# Schematic.net
KiCad netlist of a schematic drawn in Altium Designer
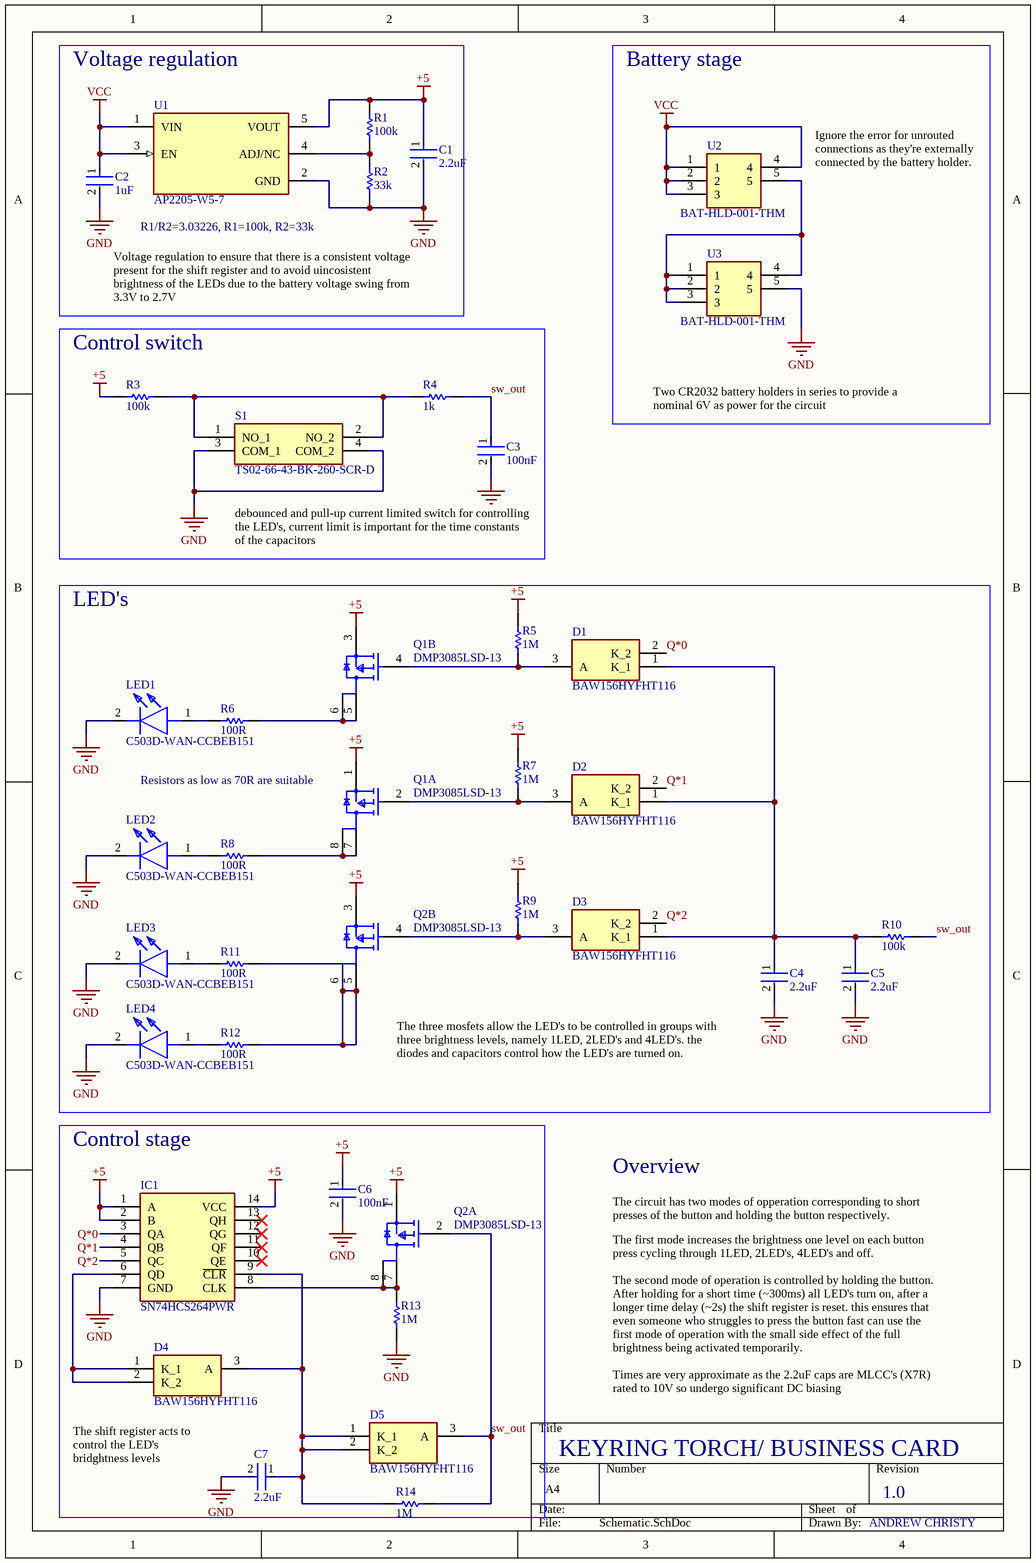
[diagram p0: Schematic.SchDoc]

(export (version "E")
  (design (tool "Eeschema 10.0.6"))
  (components
    (comp (ref "C1")
      (value "2.2uF")
      (footprint "FP-GRM188-0_1-e0_2_0_55-IPC_A")
      (description "Chip Multilayer Ceramic Capacitors for General Purpose, 0603, 10uF, X5R, 15%, 20%, 6.3V")
      (fields (field (name "VOLTAGE") "6.3V") (field (name "TOLERANCE") "20%"))
      (libsource (lib "Altium Content Vault") (part "02cd4be3c70576c341d710602a673aa"))
    )
    (comp (ref "C2")
      (value "1uF")
      (footprint "FP-GRM188-0_1-e0_2_0_55-IPC_A")
      (description "Chip Multilayer Ceramic Capacitors for General Purpose, 0603, 10uF, X5R, 15%, 20%, 6.3V")
      (fields (field (name "VOLTAGE") "6.3V") (field (name "TOLERANCE") "20%"))
      (libsource (lib "Altium Content Vault") (part "02cd4be3c70576c341d710602a673aa"))
    )
    (comp (ref "C3")
      (value "100nF")
      (footprint "FP-GRM188-0_1-e0_2_0_55-IPC_A")
      (description "Chip Multilayer Ceramic Capacitors for General Purpose, 0603, 10uF, X5R, 15%, 20%, 6.3V")
      (fields (field (name "VOLTAGE") "6.3V") (field (name "TOLERANCE") "20%"))
      (libsource (lib "Altium Content Vault") (part "02cd4be3c70576c341d710602a673aa"))
    )
    (comp (ref "C4")
      (value "2.2uF")
      (footprint "FP-GRM188-0_1-e0_2_0_55-IPC_A")
      (description "Chip Multilayer Ceramic Capacitors for General Purpose, 0603, 10uF, X5R, 15%, 20%, 6.3V")
      (fields (field (name "VOLTAGE") "6.3V") (field (name "TOLERANCE") "20%"))
      (libsource (lib "Altium Content Vault") (part "02cd4be3c70576c341d710602a673aa"))
    )
    (comp (ref "C5")
      (value "2.2uF")
      (footprint "FP-GRM188-0_1-e0_2_0_55-IPC_A")
      (description "Chip Multilayer Ceramic Capacitors for General Purpose, 0603, 10uF, X5R, 15%, 20%, 6.3V")
      (fields (field (name "VOLTAGE") "6.3V") (field (name "TOLERANCE") "20%"))
      (libsource (lib "Altium Content Vault") (part "02cd4be3c70576c341d710602a673aa"))
    )
    (comp (ref "C6")
      (value "100nF")
      (footprint "FP-GRM188-0_1-e0_2_0_55-IPC_A")
      (description "Chip Multilayer Ceramic Capacitors for General Purpose, 0603, 10uF, X5R, 15%, 20%, 6.3V")
      (fields (field (name "VOLTAGE") "6.3V") (field (name "TOLERANCE") "20%"))
      (libsource (lib "Altium Content Vault") (part "02cd4be3c70576c341d710602a673aa"))
    )
    (comp (ref "C7")
      (value "2.2uF")
      (footprint "FP-GRM188-0_1-e0_2_0_55-IPC_A")
      (description "Chip Multilayer Ceramic Capacitors for General Purpose, 0603, 10uF, X5R, 15%, 20%, 6.3V")
      (fields (field (name "VOLTAGE") "6.3V") (field (name "TOLERANCE") "20%"))
      (libsource (lib "Altium Content Vault") (part "02cd4be3c70576c341d710602a673aa"))
    )
    (comp (ref "D1")
      (value "BAW156HYFHT116")
      (footprint "SamacSys:SOT95P240X115-3N")
      (description "Diode")
      (libsource (lib "SamacSys") (part "BAW156HYFHT116"))
    )
    (comp (ref "D2")
      (value "BAW156HYFHT116")
      (footprint "SamacSys:SOT95P240X115-3N")
      (description "Diode")
      (libsource (lib "SamacSys") (part "BAW156HYFHT116"))
    )
    (comp (ref "D3")
      (value "BAW156HYFHT116")
      (footprint "SamacSys:SOT95P240X115-3N")
      (description "Diode")
      (libsource (lib "SamacSys") (part "BAW156HYFHT116"))
    )
    (comp (ref "D4")
      (value "BAW156HYFHT116")
      (footprint "SamacSys:SOT95P240X115-3N")
      (description "Diode")
      (libsource (lib "") (part "BAW156HYFHT116_1"))
    )
    (comp (ref "D5")
      (value "BAW156HYFHT116")
      (footprint "SamacSys:SOT95P240X115-3N")
      (description "Diode")
      (libsource (lib "") (part "BAW156HYFHT116_1"))
    )
    (comp (ref "IC1")
      (value "SN74HCS264PWR")
      (footprint "SamacSys:SOP65P640X120-14N")
      (description "Integrated Circuit")
      (fields (field (name "MOUSER PART NUMBER") "595-SN74HCS264PWR"))
      (libsource (lib "SamacSys") (part "SN74HCS264PWR"))
    )
    (comp (ref "LED1")
      (value "C503D-WAN-CCBEB151")
      (footprint "SamacSys:C503DWANCCBEB151")
      (description "LED")
      (fields (field (name "MOUSER PART NUMBER") "941-C503DWANCCBEB151"))
      (libsource (lib "SamacSys") (part "C503D-WAN-CCBEB151"))
    )
    (comp (ref "LED2")
      (value "C503D-WAN-CCBEB151")
      (footprint "SamacSys:C503DWANCCBEB151")
      (description "LED")
      (fields (field (name "MOUSER PART NUMBER") "941-C503DWANCCBEB151"))
      (libsource (lib "SamacSys") (part "C503D-WAN-CCBEB151"))
    )
    (comp (ref "LED3")
      (value "C503D-WAN-CCBEB151")
      (footprint "SamacSys:C503DWANCCBEB151")
      (description "LED")
      (fields (field (name "MOUSER PART NUMBER") "941-C503DWANCCBEB151"))
      (libsource (lib "SamacSys") (part "C503D-WAN-CCBEB151"))
    )
    (comp (ref "LED4")
      (value "C503D-WAN-CCBEB151")
      (footprint "SamacSys:C503DWANCCBEB151")
      (description "LED")
      (fields (field (name "MOUSER PART NUMBER") "941-C503DWANCCBEB151"))
      (libsource (lib "SamacSys") (part "C503D-WAN-CCBEB151"))
    )
    (comp (ref "Q1")
      (value "DMP3085LSD-13")
      (footprint "FP-SO-8-MFG")
      (description "MOSFET 2P-CH 30V 3.9A 8SO")
      (fields
        (field (name "OCTOPART") "https://octopart.com/dmp3085lsd-13-diodes+inc.-29925597")
        (field (name "MANUFACTURER") "Diodes Inc.")
      )
      (libsource (lib "Altium Content Vault") (part "942955f0223a51ca7db3cf2ab639610"))
    )
    (comp (ref "Q2")
      (value "DMP3085LSD-13")
      (footprint "FP-SO-8-MFG")
      (description "MOSFET 2P-CH 30V 3.9A 8SO")
      (fields
        (field (name "OCTOPART") "https://octopart.com/dmp3085lsd-13-diodes+inc.-29925597")
        (field (name "MANUFACTURER") "Diodes Inc.")
      )
      (libsource (lib "Altium Content Vault") (part "942955f0223a51ca7db3cf2ab639610"))
    )
    (comp (ref "R1")
      (value "100k")
      (footprint "RESC1609X50X30NL8T20")
      (description "Chip Resistor, 0 Ohm, Jumper, 100 mW, -55 to 155 degC, 0603 (1608 Metric), RoHS, Tape and Reel")
      (fields (field (name "MANUFACTURER") "Vishay Semiconductor"))
      (libsource (lib "Altium Content Vault") (part "RES-2"))
    )
    (comp (ref "R2")
      (value "33k")
      (footprint "RESC1609X50X30NL8T20")
      (description "Chip Resistor, 0 Ohm, Jumper, 100 mW, -55 to 155 degC, 0603 (1608 Metric), RoHS, Tape and Reel")
      (fields (field (name "MANUFACTURER") "Vishay Semiconductor"))
      (libsource (lib "Altium Content Vault") (part "RES-2"))
    )
    (comp (ref "R3")
      (value "100k")
      (footprint "RESC1609X50X30NL8T20")
      (description "Chip Resistor, 0 Ohm, Jumper, 100 mW, -55 to 155 degC, 0603 (1608 Metric), RoHS, Tape and Reel")
      (fields (field (name "MANUFACTURER") "Vishay Semiconductor"))
      (libsource (lib "Altium Content Vault") (part "RES-2"))
    )
    (comp (ref "R4")
      (value "1k")
      (footprint "RESC1609X50X30NL8T20")
      (description "Chip Resistor, 0 Ohm, Jumper, 100 mW, -55 to 155 degC, 0603 (1608 Metric), RoHS, Tape and Reel")
      (fields (field (name "MANUFACTURER") "Vishay Semiconductor"))
      (libsource (lib "Altium Content Vault") (part "RES-2"))
    )
    (comp (ref "R5")
      (value "1M")
      (footprint "RESC1609X50X30NL8T20")
      (description "Chip Resistor, 0 Ohm, Jumper, 100 mW, -55 to 155 degC, 0603 (1608 Metric), RoHS, Tape and Reel")
      (fields (field (name "MANUFACTURER") "Vishay Semiconductor"))
      (libsource (lib "Altium Content Vault") (part "RES-2"))
    )
    (comp (ref "R6")
      (value "100R")
      (footprint "RESC1609X50X30NL8T20")
      (description "Chip Resistor, 0 Ohm, Jumper, 100 mW, -55 to 155 degC, 0603 (1608 Metric), RoHS, Tape and Reel")
      (fields (field (name "MANUFACTURER") "Vishay Semiconductor"))
      (libsource (lib "Altium Content Vault") (part "RES-2"))
    )
    (comp (ref "R7")
      (value "1M")
      (footprint "RESC1609X50X30NL8T20")
      (description "Chip Resistor, 0 Ohm, Jumper, 100 mW, -55 to 155 degC, 0603 (1608 Metric), RoHS, Tape and Reel")
      (fields (field (name "MANUFACTURER") "Vishay Semiconductor"))
      (libsource (lib "Altium Content Vault") (part "RES-2"))
    )
    (comp (ref "R8")
      (value "100R")
      (footprint "RESC1609X50X30NL8T20")
      (description "Chip Resistor, 0 Ohm, Jumper, 100 mW, -55 to 155 degC, 0603 (1608 Metric), RoHS, Tape and Reel")
      (fields (field (name "MANUFACTURER") "Vishay Semiconductor"))
      (libsource (lib "Altium Content Vault") (part "RES-2"))
    )
    (comp (ref "R9")
      (value "1M")
      (footprint "RESC1609X50X30NL8T20")
      (description "Chip Resistor, 0 Ohm, Jumper, 100 mW, -55 to 155 degC, 0603 (1608 Metric), RoHS, Tape and Reel")
      (fields (field (name "MANUFACTURER") "Vishay Semiconductor"))
      (libsource (lib "Altium Content Vault") (part "RES-2"))
    )
    (comp (ref "R10")
      (value "100k")
      (footprint "RESC1609X50X30NL8T20")
      (description "Chip Resistor, 0 Ohm, Jumper, 100 mW, -55 to 155 degC, 0603 (1608 Metric), RoHS, Tape and Reel")
      (fields (field (name "MANUFACTURER") "Vishay Semiconductor"))
      (libsource (lib "Altium Content Vault") (part "RES-2"))
    )
    (comp (ref "R11")
      (value "100R")
      (footprint "RESC1609X50X30NL8T20")
      (description "Chip Resistor, 0 Ohm, Jumper, 100 mW, -55 to 155 degC, 0603 (1608 Metric), RoHS, Tape and Reel")
      (fields (field (name "MANUFACTURER") "Vishay Semiconductor"))
      (libsource (lib "Altium Content Vault") (part "RES-2"))
    )
    (comp (ref "R12")
      (value "100R")
      (footprint "RESC1609X50X30NL8T20")
      (description "Chip Resistor, 0 Ohm, Jumper, 100 mW, -55 to 155 degC, 0603 (1608 Metric), RoHS, Tape and Reel")
      (fields (field (name "MANUFACTURER") "Vishay Semiconductor"))
      (libsource (lib "Altium Content Vault") (part "RES-2"))
    )
    (comp (ref "R13")
      (value "1M")
      (footprint "RESC1609X50X30NL8T20")
      (description "Chip Resistor, 0 Ohm, Jumper, 100 mW, -55 to 155 degC, 0603 (1608 Metric), RoHS, Tape and Reel")
      (fields (field (name "MANUFACTURER") "Vishay Semiconductor"))
      (libsource (lib "Altium Content Vault") (part "RES-2"))
    )
    (comp (ref "R14")
      (value "1M")
      (footprint "RESC1609X50X30NL8T20")
      (description "Chip Resistor, 0 Ohm, Jumper, 100 mW, -55 to 155 degC, 0603 (1608 Metric), RoHS, Tape and Reel")
      (fields (field (name "MANUFACTURER") "Vishay Semiconductor"))
      (libsource (lib "Altium Content Vault") (part "RES-2"))
    )
    (comp (ref "S1")
      (value "TS02-66-43-BK-260-SCR-D")
      (footprint "SamacSys:TS026643BK260SCRD")
      (description "Switch")
      (fields (field (name "MOUSER PART NUMBER") "179-TS026643BK260SCR"))
      (libsource (lib "*") (part "TS02-66-43-BK-260-SCR-D"))
    )
    (comp (ref "U1")
      (value "AP2205-W5-7")
      (footprint "FP-SOT25-MFG")
      (description "IC REG LIN POS ADJ 250MA SOT25")
      (libsource (lib "Altium Content Vault") (part "9429a982aa183f21bc275fe3b3339f7"))
    )
    (comp (ref "U2")
      (value "BAT-HLD-001-THM")
      (footprint "SamacSys:BATHLD001THM")
      (description "Undefined or Miscellaneous")
      (fields (field (name "MOUSER PART NUMBER") "712-BAT-HLD-001-THM"))
      (libsource (lib "*") (part "BAT-HLD-001-THM"))
    )
    (comp (ref "U3")
      (value "BAT-HLD-001-THM")
      (footprint "SamacSys:BATHLD001THM")
      (description "Undefined or Miscellaneous")
      (fields (field (name "MOUSER PART NUMBER") "712-BAT-HLD-001-THM"))
      (libsource (lib "*") (part "BAT-HLD-001-THM"))
    )
  )
  (nets
    (net (code "1") (name "+5") (class "Default")
      (node (ref "C1") (pin "1") (pinfunction "1_1") (pintype "passive"))
      (node (ref "C6") (pin "1") (pinfunction "1_1") (pintype "passive"))
      (node (ref "IC1") (pin "1") (pinfunction "A_1") (pintype "passive"))
      (node (ref "IC1") (pin "14") (pinfunction "VCC_14") (pintype "passive"))
      (node (ref "IC1") (pin "2") (pinfunction "B_2") (pintype "passive"))
      (node (ref "Q1") (pin "1") (pinfunction "S1_1") (pintype "passive"))
      (node (ref "Q1") (pin "3") (pinfunction "S2_3") (pintype "passive"))
      (node (ref "Q2") (pin "1") (pinfunction "S1_1") (pintype "passive"))
      (node (ref "Q2") (pin "3") (pinfunction "S2_3") (pintype "passive"))
      (node (ref "R1") (pin "2") (pinfunction "2_2") (pintype "passive"))
      (node (ref "R3") (pin "2") (pinfunction "2_2") (pintype "passive"))
      (node (ref "R5") (pin "2") (pinfunction "2_2") (pintype "passive"))
      (node (ref "R7") (pin "2") (pinfunction "2_2") (pintype "passive"))
      (node (ref "R9") (pin "2") (pinfunction "2_2") (pintype "passive"))
      (node (ref "U1") (pin "5") (pinfunction "VOUT_5") (pintype "power_in"))
    )
    (net (code "2") (name "/Q*0") (class "Default")
      (node (ref "D1") (pin "2") (pinfunction "K_2_2") (pintype "passive"))
      (node (ref "IC1") (pin "3") (pinfunction "QA_3") (pintype "passive"))
    )
    (net (code "3") (name "/Q*1") (class "Default")
      (node (ref "D2") (pin "2") (pinfunction "K_2_2") (pintype "passive"))
      (node (ref "IC1") (pin "4") (pinfunction "QB_4") (pintype "passive"))
    )
    (net (code "4") (name "/Q*2") (class "Default")
      (node (ref "D3") (pin "2") (pinfunction "K_2_2") (pintype "passive"))
      (node (ref "IC1") (pin "5") (pinfunction "QC_5") (pintype "passive"))
    )
    (net (code "5") (name "/sw_out") (class "Default")
      (node (ref "C3") (pin "1") (pinfunction "1_1") (pintype "passive"))
      (node (ref "D5") (pin "3") (pinfunction "A_3") (pintype "passive"))
      (node (ref "Q2") (pin "2") (pinfunction "G1_2") (pintype "passive"))
      (node (ref "R10") (pin "1") (pinfunction "1_1") (pintype "passive"))
      (node (ref "R14") (pin "1") (pinfunction "1_1") (pintype "passive"))
      (node (ref "R4") (pin "1") (pinfunction "1_1") (pintype "passive"))
    )
    (net (code "6") (name "GND") (class "Default")
      (node (ref "C1") (pin "2") (pinfunction "2_2") (pintype "passive"))
      (node (ref "C2") (pin "2") (pinfunction "2_2") (pintype "passive"))
      (node (ref "C3") (pin "2") (pinfunction "2_2") (pintype "passive"))
      (node (ref "C4") (pin "2") (pinfunction "2_2") (pintype "passive"))
      (node (ref "C5") (pin "2") (pinfunction "2_2") (pintype "passive"))
      (node (ref "C6") (pin "2") (pinfunction "2_2") (pintype "passive"))
      (node (ref "C7") (pin "2") (pinfunction "2_2") (pintype "passive"))
      (node (ref "IC1") (pin "7") (pinfunction "GND_7") (pintype "passive"))
      (node (ref "LED1") (pin "2") (pinfunction "K_2") (pintype "passive"))
      (node (ref "LED2") (pin "2") (pinfunction "K_2") (pintype "passive"))
      (node (ref "LED3") (pin "2") (pinfunction "K_2") (pintype "passive"))
      (node (ref "LED4") (pin "2") (pinfunction "K_2") (pintype "passive"))
      (node (ref "R13") (pin "1") (pinfunction "1_1") (pintype "passive"))
      (node (ref "R2") (pin "1") (pinfunction "1_1") (pintype "passive"))
      (node (ref "S1") (pin "3") (pinfunction "COM_1_3") (pintype "passive"))
      (node (ref "S1") (pin "4") (pinfunction "COM_2_4") (pintype "passive"))
      (node (ref "U1") (pin "2") (pinfunction "GND_2") (pintype "power_in"))
      (node (ref "U3") (pin "5") (pinfunction "5_5") (pintype "passive"))
    )
    (net (code "7") (name "Net-(D1-A)") (class "Default")
      (node (ref "D1") (pin "3") (pinfunction "A_3") (pintype "passive"))
      (node (ref "Q1") (pin "4") (pinfunction "G2_4") (pintype "passive"))
      (node (ref "R5") (pin "1") (pinfunction "1_1") (pintype "passive"))
    )
    (net (code "8") (name "Net-(D1-K_1)") (class "Default")
      (node (ref "C4") (pin "1") (pinfunction "1_1") (pintype "passive"))
      (node (ref "C5") (pin "1") (pinfunction "1_1") (pintype "passive"))
      (node (ref "D1") (pin "1") (pinfunction "K_1_1") (pintype "passive"))
      (node (ref "D2") (pin "1") (pinfunction "K_1_1") (pintype "passive"))
      (node (ref "D3") (pin "1") (pinfunction "K_1_1") (pintype "passive"))
      (node (ref "R10") (pin "2") (pinfunction "2_2") (pintype "passive"))
    )
    (net (code "9") (name "Net-(D2-A)") (class "Default")
      (node (ref "D2") (pin "3") (pinfunction "A_3") (pintype "passive"))
      (node (ref "Q1") (pin "2") (pinfunction "G1_2") (pintype "passive"))
      (node (ref "R7") (pin "1") (pinfunction "1_1") (pintype "passive"))
    )
    (net (code "10") (name "Net-(D3-A)") (class "Default")
      (node (ref "D3") (pin "3") (pinfunction "A_3") (pintype "passive"))
      (node (ref "Q2") (pin "4") (pinfunction "G2_4") (pintype "passive"))
      (node (ref "R9") (pin "1") (pinfunction "1_1") (pintype "passive"))
    )
    (net (code "11") (name "Net-(D4-A)") (class "Default")
      (node (ref "C7") (pin "1") (pinfunction "1_1") (pintype "passive"))
      (node (ref "D4") (pin "3") (pinfunction "A_3") (pintype "passive"))
      (node (ref "D5") (pin "1") (pinfunction "K_1_1") (pintype "passive"))
      (node (ref "D5") (pin "2") (pinfunction "K_2_2") (pintype "passive"))
      (node (ref "IC1") (pin "9") (pinfunction "~{CLR}_9") (pintype "passive"))
      (node (ref "R14") (pin "2") (pinfunction "2_2") (pintype "passive"))
    )
    (net (code "12") (name "Net-(D4-K_1)") (class "Default")
      (node (ref "D4") (pin "1") (pinfunction "K_1_1") (pintype "passive"))
      (node (ref "D4") (pin "2") (pinfunction "K_2_2") (pintype "passive"))
      (node (ref "IC1") (pin "6") (pinfunction "QD_6") (pintype "passive"))
    )
    (net (code "13") (name "Net-(IC1-CLK)") (class "Default")
      (node (ref "IC1") (pin "8") (pinfunction "CLK_8") (pintype "passive"))
      (node (ref "Q2") (pin "7") (pinfunction "D1_7") (pintype "passive"))
      (node (ref "Q2") (pin "8") (pinfunction "D1_8") (pintype "passive"))
      (node (ref "R13") (pin "2") (pinfunction "2_2") (pintype "passive"))
    )
    (net (code "14") (name "Net-(LED1-A)") (class "Default")
      (node (ref "LED1") (pin "1") (pinfunction "A_1") (pintype "passive"))
      (node (ref "R6") (pin "2") (pinfunction "2_2") (pintype "passive"))
    )
    (net (code "15") (name "Net-(LED2-A)") (class "Default")
      (node (ref "LED2") (pin "1") (pinfunction "A_1") (pintype "passive"))
      (node (ref "R8") (pin "2") (pinfunction "2_2") (pintype "passive"))
    )
    (net (code "16") (name "Net-(LED3-A)") (class "Default")
      (node (ref "LED3") (pin "1") (pinfunction "A_1") (pintype "passive"))
      (node (ref "R11") (pin "2") (pinfunction "2_2") (pintype "passive"))
    )
    (net (code "17") (name "Net-(LED4-A)") (class "Default")
      (node (ref "LED4") (pin "1") (pinfunction "A_1") (pintype "passive"))
      (node (ref "R12") (pin "2") (pinfunction "2_2") (pintype "passive"))
    )
    (net (code "18") (name "Net-(Q1A-D1-Pad7)") (class "Default")
      (node (ref "Q1") (pin "7") (pinfunction "D1_7") (pintype "passive"))
      (node (ref "Q1") (pin "8") (pinfunction "D1_8") (pintype "passive"))
      (node (ref "R8") (pin "1") (pinfunction "1_1") (pintype "passive"))
    )
    (net (code "19") (name "Net-(Q1B-D2-Pad5)") (class "Default")
      (node (ref "Q1") (pin "5") (pinfunction "D2_5") (pintype "passive"))
      (node (ref "Q1") (pin "6") (pinfunction "D2_6") (pintype "passive"))
      (node (ref "R6") (pin "1") (pinfunction "1_1") (pintype "passive"))
    )
    (net (code "20") (name "Net-(Q2B-D2-Pad5)") (class "Default")
      (node (ref "Q2") (pin "5") (pinfunction "D2_5") (pintype "passive"))
      (node (ref "Q2") (pin "6") (pinfunction "D2_6") (pintype "passive"))
      (node (ref "R11") (pin "1") (pinfunction "1_1") (pintype "passive"))
      (node (ref "R12") (pin "1") (pinfunction "1_1") (pintype "passive"))
    )
    (net (code "21") (name "Net-(S1-NO_1)") (class "Default")
      (node (ref "R3") (pin "1") (pinfunction "1_1") (pintype "passive"))
      (node (ref "R4") (pin "2") (pinfunction "2_2") (pintype "passive"))
      (node (ref "S1") (pin "1") (pinfunction "NO_1_1") (pintype "passive"))
      (node (ref "S1") (pin "2") (pinfunction "NO_2_2") (pintype "passive"))
    )
    (net (code "22") (name "Net-(U1-ADJ{slash}NC)") (class "Default")
      (node (ref "R1") (pin "1") (pinfunction "1_1") (pintype "passive"))
      (node (ref "R2") (pin "2") (pinfunction "2_2") (pintype "passive"))
      (node (ref "U1") (pin "4") (pinfunction "ADJ/NC_4") (pintype "passive"))
    )
    (net (code "23") (name "Net-(U2-Pad5)") (class "Default")
      (node (ref "U2") (pin "5") (pinfunction "5_5") (pintype "passive"))
      (node (ref "U3") (pin "1") (pinfunction "1_1") (pintype "passive"))
      (node (ref "U3") (pin "2") (pinfunction "2_2") (pintype "passive"))
      (node (ref "U3") (pin "3") (pinfunction "3_3") (pintype "passive"))
      (node (ref "U3") (pin "4") (pinfunction "4_4") (pintype "passive"))
    )
    (net (code "24") (name "VCC") (class "Default")
      (node (ref "C2") (pin "1") (pinfunction "1_1") (pintype "passive"))
      (node (ref "U1") (pin "1") (pinfunction "VIN_1") (pintype "power_in"))
      (node (ref "U1") (pin "3") (pinfunction "EN_3") (pintype "input"))
      (node (ref "U2") (pin "1") (pinfunction "1_1") (pintype "passive"))
      (node (ref "U2") (pin "2") (pinfunction "2_2") (pintype "passive"))
      (node (ref "U2") (pin "3") (pinfunction "3_3") (pintype "passive"))
      (node (ref "U2") (pin "4") (pinfunction "4_4") (pintype "passive"))
    )
    (net (code "25") (name "unconnected-(IC1-QE-Pad10)") (class "Default")
      (node (ref "IC1") (pin "10") (pinfunction "QE_10") (pintype "passive+no_connect"))
    )
    (net (code "26") (name "unconnected-(IC1-QF-Pad11)") (class "Default")
      (node (ref "IC1") (pin "11") (pinfunction "QF_11") (pintype "passive+no_connect"))
    )
    (net (code "27") (name "unconnected-(IC1-QG-Pad12)") (class "Default")
      (node (ref "IC1") (pin "12") (pinfunction "QG_12") (pintype "passive+no_connect"))
    )
    (net (code "28") (name "unconnected-(IC1-QH-Pad13)") (class "Default")
      (node (ref "IC1") (pin "13") (pinfunction "QH_13") (pintype "passive+no_connect"))
    )
  )
)
